# SPI_Board.net
KiCad netlist of a schematic drawn in Altium Designer
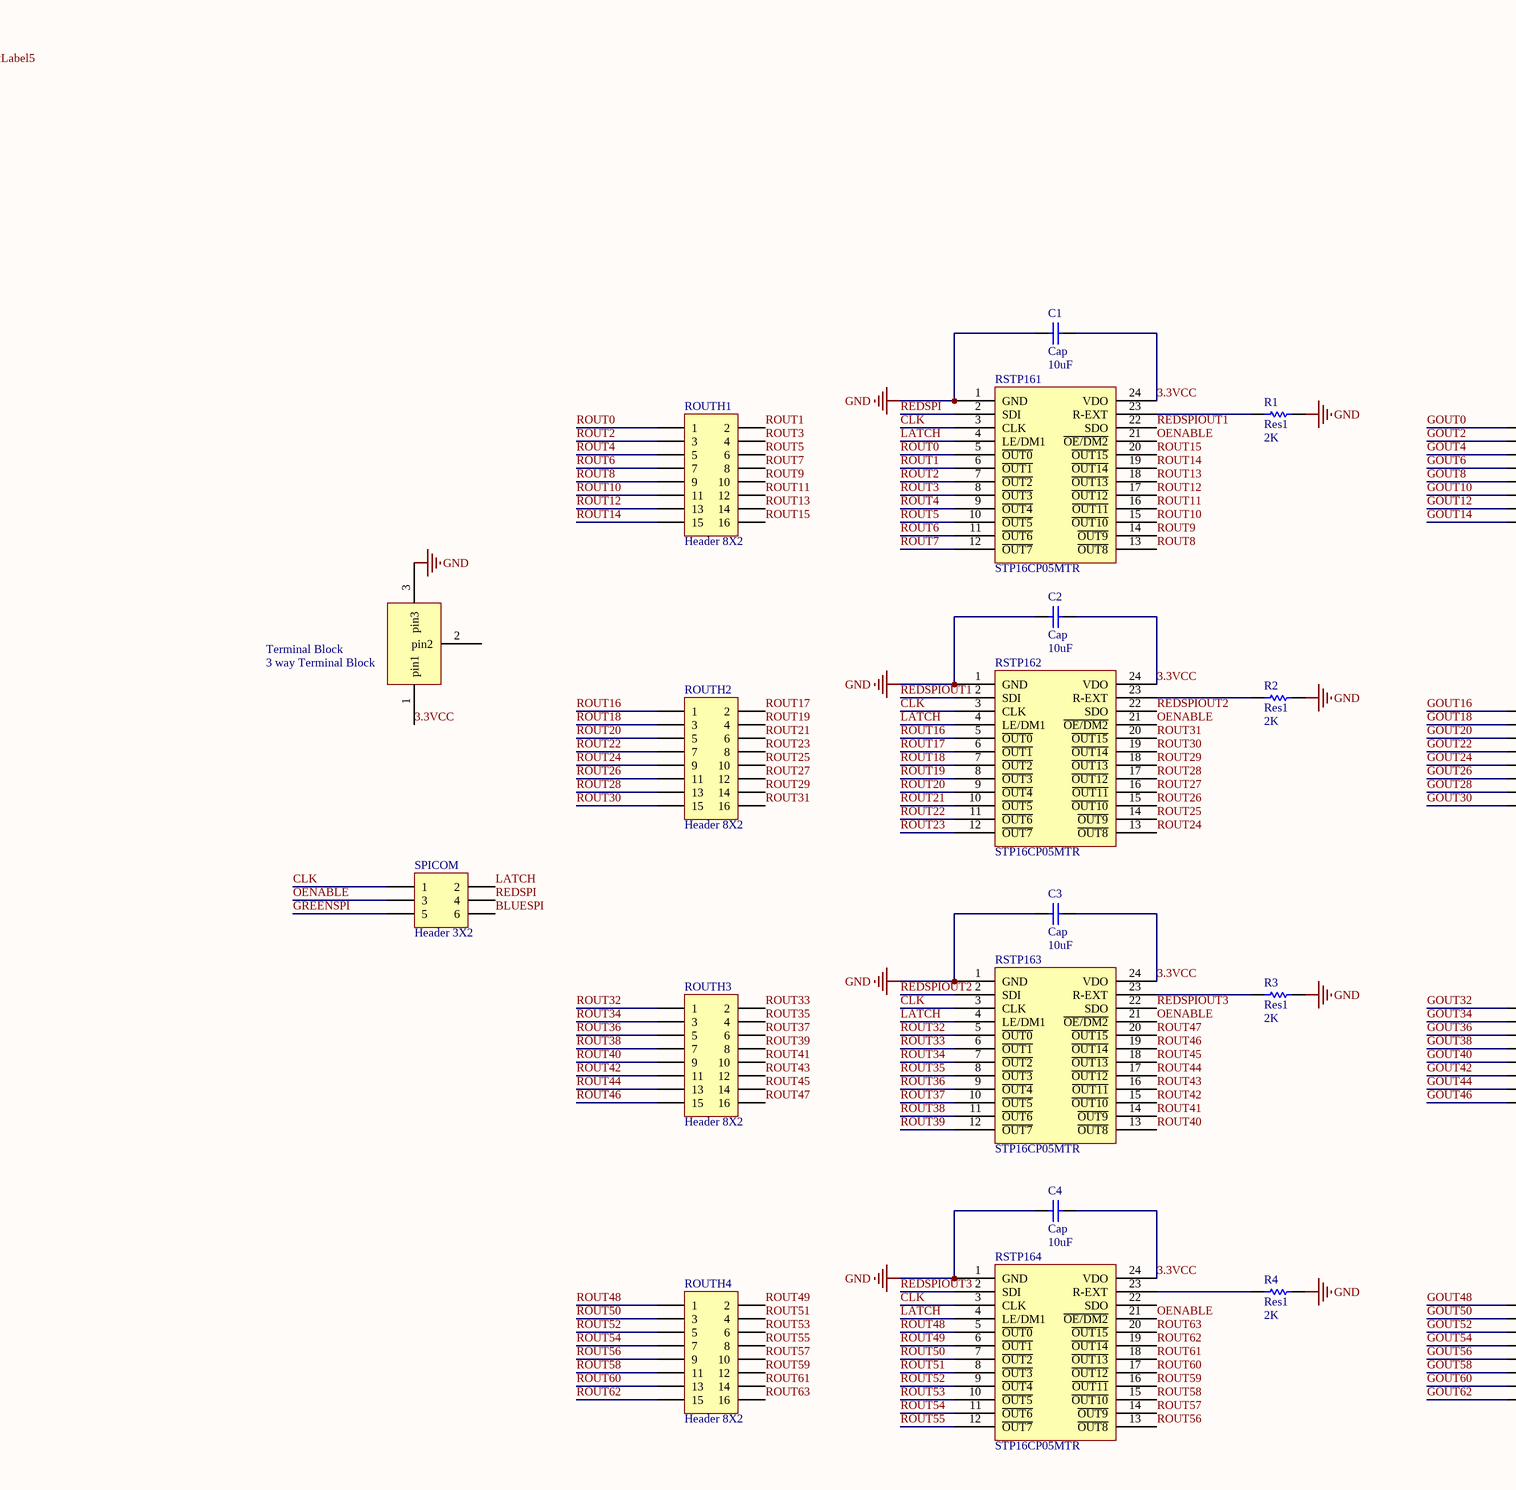
[diagram p0: SPI_Board.SchDoc, left]
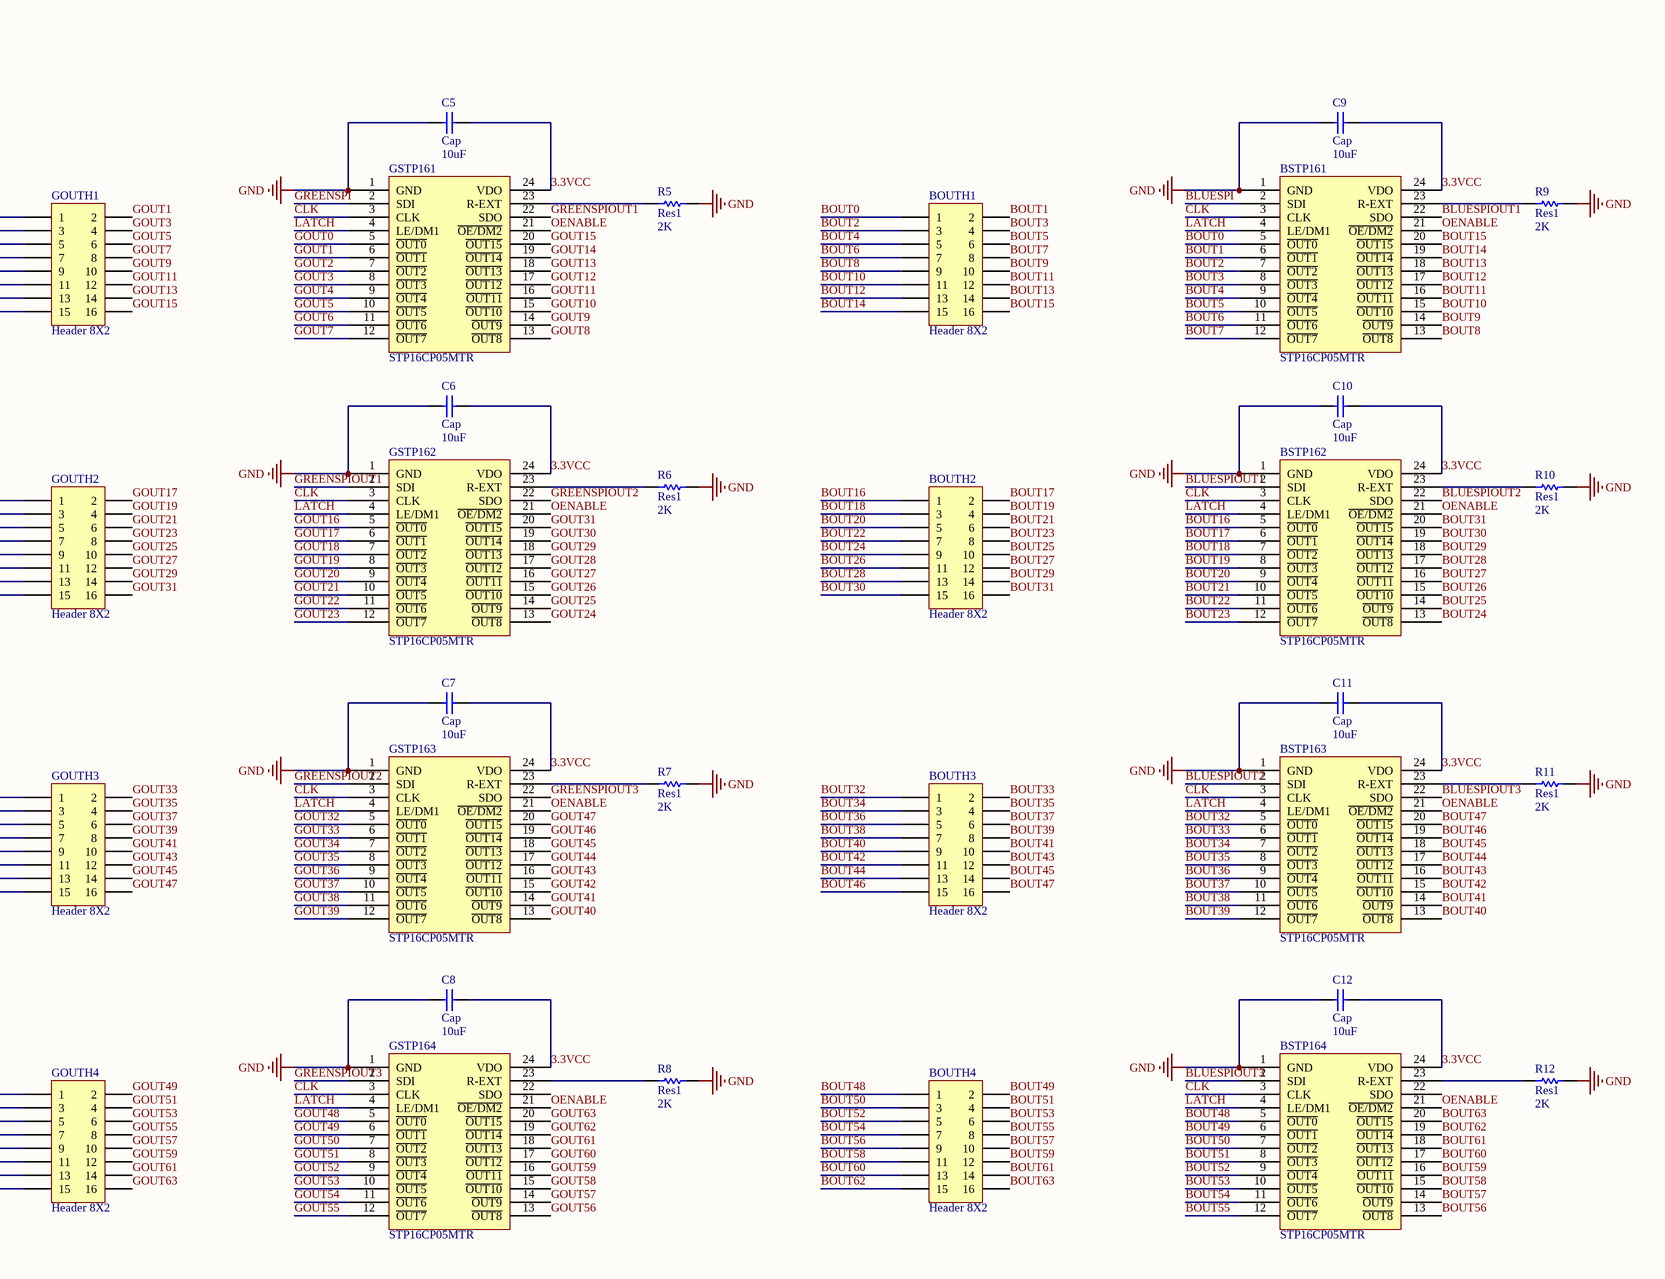
[diagram p1: SPI_Board.SchDoc, right]

(export (version "E")
  (design (tool "Eeschema 10.0.6"))
  (components
    (comp (ref "BOUTH1")
      (value "Header 8X2")
      (footprint "HDR2X8")
      (description "Header, 8-Pin, Dual row")
      (fields (field (name "PUBLISHER") "Altium Limited"))
      (libsource (lib "Miscellaneous Connectors") (part "Header 8X2"))
    )
    (comp (ref "BOUTH2")
      (value "Header 8X2")
      (footprint "HDR2X8")
      (description "Header, 8-Pin, Dual row")
      (fields (field (name "PUBLISHER") "Altium Limited"))
      (libsource (lib "Miscellaneous Connectors") (part "Header 8X2"))
    )
    (comp (ref "BOUTH3")
      (value "Header 8X2")
      (footprint "HDR2X8")
      (description "Header, 8-Pin, Dual row")
      (fields (field (name "PUBLISHER") "Altium Limited"))
      (libsource (lib "Miscellaneous Connectors") (part "Header 8X2"))
    )
    (comp (ref "BOUTH4")
      (value "Header 8X2")
      (footprint "HDR2X8")
      (description "Header, 8-Pin, Dual row")
      (fields (field (name "PUBLISHER") "Altium Limited"))
      (libsource (lib "Miscellaneous Connectors") (part "Header 8X2"))
    )
    (comp (ref "BSTP161")
      (value "STP16CP05MTR")
      (footprint "STP16CP05MTR-24N")
      (libsource (lib "STP16CP05MTR") (part "STP16CP05MTR"))
    )
    (comp (ref "BSTP162")
      (value "STP16CP05MTR")
      (footprint "STP16CP05MTR-24N")
      (libsource (lib "STP16CP05MTR") (part "STP16CP05MTR"))
    )
    (comp (ref "BSTP163")
      (value "STP16CP05MTR")
      (footprint "STP16CP05MTR-24N")
      (libsource (lib "STP16CP05MTR") (part "STP16CP05MTR"))
    )
    (comp (ref "BSTP164")
      (value "STP16CP05MTR")
      (footprint "STP16CP05MTR-24N")
      (libsource (lib "STP16CP05MTR") (part "STP16CP05MTR"))
    )
    (comp (ref "C1")
      (value "Cap")
      (footprint "RAD0.2A")
      (description "Capacitor")
      (fields (field (name "ALTIUM_VALUE") "10uF") (field (name "PUBLISHER") "Altium Limited"))
      (libsource (lib "Miscellaneous Devices") (part "Cap"))
    )
    (comp (ref "C2")
      (value "Cap")
      (footprint "RAD0.2A")
      (description "Capacitor")
      (fields (field (name "ALTIUM_VALUE") "10uF") (field (name "PUBLISHER") "Altium Limited"))
      (libsource (lib "Miscellaneous Devices") (part "Cap"))
    )
    (comp (ref "C3")
      (value "Cap")
      (footprint "RAD0.2A")
      (description "Capacitor")
      (fields (field (name "ALTIUM_VALUE") "10uF") (field (name "PUBLISHER") "Altium Limited"))
      (libsource (lib "Miscellaneous Devices") (part "Cap"))
    )
    (comp (ref "C4")
      (value "Cap")
      (footprint "RAD0.2A")
      (description "Capacitor")
      (fields (field (name "ALTIUM_VALUE") "10uF") (field (name "PUBLISHER") "Altium Limited"))
      (libsource (lib "Miscellaneous Devices") (part "Cap"))
    )
    (comp (ref "C5")
      (value "Cap")
      (footprint "RAD0.2A")
      (description "Capacitor")
      (fields (field (name "ALTIUM_VALUE") "10uF") (field (name "PUBLISHER") "Altium Limited"))
      (libsource (lib "Miscellaneous Devices") (part "Cap"))
    )
    (comp (ref "C6")
      (value "Cap")
      (footprint "RAD0.2A")
      (description "Capacitor")
      (fields (field (name "ALTIUM_VALUE") "10uF") (field (name "PUBLISHER") "Altium Limited"))
      (libsource (lib "Miscellaneous Devices") (part "Cap"))
    )
    (comp (ref "C7")
      (value "Cap")
      (footprint "RAD0.2A")
      (description "Capacitor")
      (fields (field (name "ALTIUM_VALUE") "10uF") (field (name "PUBLISHER") "Altium Limited"))
      (libsource (lib "Miscellaneous Devices") (part "Cap"))
    )
    (comp (ref "C8")
      (value "Cap")
      (footprint "RAD0.2A")
      (description "Capacitor")
      (fields (field (name "ALTIUM_VALUE") "10uF") (field (name "PUBLISHER") "Altium Limited"))
      (libsource (lib "Miscellaneous Devices") (part "Cap"))
    )
    (comp (ref "C9")
      (value "Cap")
      (footprint "RAD0.2A")
      (description "Capacitor")
      (fields (field (name "ALTIUM_VALUE") "10uF") (field (name "PUBLISHER") "Altium Limited"))
      (libsource (lib "Miscellaneous Devices") (part "Cap"))
    )
    (comp (ref "C10")
      (value "Cap")
      (footprint "RAD0.2A")
      (description "Capacitor")
      (fields (field (name "ALTIUM_VALUE") "10uF") (field (name "PUBLISHER") "Altium Limited"))
      (libsource (lib "Miscellaneous Devices") (part "Cap"))
    )
    (comp (ref "C11")
      (value "Cap")
      (footprint "RAD0.2A")
      (description "Capacitor")
      (fields (field (name "ALTIUM_VALUE") "10uF") (field (name "PUBLISHER") "Altium Limited"))
      (libsource (lib "Miscellaneous Devices") (part "Cap"))
    )
    (comp (ref "C12")
      (value "Cap")
      (footprint "RAD0.2A")
      (description "Capacitor")
      (fields (field (name "ALTIUM_VALUE") "10uF") (field (name "PUBLISHER") "Altium Limited"))
      (libsource (lib "Miscellaneous Devices") (part "Cap"))
    )
    (comp (ref "GOUTH1")
      (value "Header 8X2")
      (footprint "HDR2X8")
      (description "Header, 8-Pin, Dual row")
      (fields (field (name "PUBLISHER") "Altium Limited"))
      (libsource (lib "Miscellaneous Connectors") (part "Header 8X2"))
    )
    (comp (ref "GOUTH2")
      (value "Header 8X2")
      (footprint "HDR2X8")
      (description "Header, 8-Pin, Dual row")
      (fields (field (name "PUBLISHER") "Altium Limited"))
      (libsource (lib "Miscellaneous Connectors") (part "Header 8X2"))
    )
    (comp (ref "GOUTH3")
      (value "Header 8X2")
      (footprint "HDR2X8")
      (description "Header, 8-Pin, Dual row")
      (fields (field (name "PUBLISHER") "Altium Limited"))
      (libsource (lib "Miscellaneous Connectors") (part "Header 8X2"))
    )
    (comp (ref "GOUTH4")
      (value "Header 8X2")
      (footprint "HDR2X8")
      (description "Header, 8-Pin, Dual row")
      (fields (field (name "PUBLISHER") "Altium Limited"))
      (libsource (lib "Miscellaneous Connectors") (part "Header 8X2"))
    )
    (comp (ref "GSTP161")
      (value "STP16CP05MTR")
      (footprint "STP16CP05MTR-24N")
      (libsource (lib "STP16CP05MTR") (part "STP16CP05MTR"))
    )
    (comp (ref "GSTP162")
      (value "STP16CP05MTR")
      (footprint "STP16CP05MTR-24N")
      (libsource (lib "STP16CP05MTR") (part "STP16CP05MTR"))
    )
    (comp (ref "GSTP163")
      (value "STP16CP05MTR")
      (footprint "STP16CP05MTR-24N")
      (libsource (lib "STP16CP05MTR") (part "STP16CP05MTR"))
    )
    (comp (ref "GSTP164")
      (value "STP16CP05MTR")
      (footprint "STP16CP05MTR-24N")
      (libsource (lib "STP16CP05MTR") (part "STP16CP05MTR"))
    )
    (comp (ref "R1")
      (value "Res1")
      (footprint "AXIAL0.4")
      (description "Resistor")
      (fields (field (name "ALTIUM_VALUE") "2K") (field (name "PUBLISHER") "Altium Limited"))
      (libsource (lib "Miscellaneous Devices") (part "Res1"))
    )
    (comp (ref "R2")
      (value "Res1")
      (footprint "AXIAL0.4")
      (description "Resistor")
      (fields (field (name "ALTIUM_VALUE") "2K") (field (name "PUBLISHER") "Altium Limited"))
      (libsource (lib "Miscellaneous Devices") (part "Res1"))
    )
    (comp (ref "R3")
      (value "Res1")
      (footprint "AXIAL0.4")
      (description "Resistor")
      (fields (field (name "ALTIUM_VALUE") "2K") (field (name "PUBLISHER") "Altium Limited"))
      (libsource (lib "Miscellaneous Devices") (part "Res1"))
    )
    (comp (ref "R4")
      (value "Res1")
      (footprint "AXIAL0.4")
      (description "Resistor")
      (fields (field (name "ALTIUM_VALUE") "2K") (field (name "PUBLISHER") "Altium Limited"))
      (libsource (lib "Miscellaneous Devices") (part "Res1"))
    )
    (comp (ref "R5")
      (value "Res1")
      (footprint "AXIAL0.4")
      (description "Resistor")
      (fields (field (name "ALTIUM_VALUE") "2K") (field (name "PUBLISHER") "Altium Limited"))
      (libsource (lib "Miscellaneous Devices") (part "Res1"))
    )
    (comp (ref "R6")
      (value "Res1")
      (footprint "AXIAL0.4")
      (description "Resistor")
      (fields (field (name "ALTIUM_VALUE") "2K") (field (name "PUBLISHER") "Altium Limited"))
      (libsource (lib "Miscellaneous Devices") (part "Res1"))
    )
    (comp (ref "R7")
      (value "Res1")
      (footprint "AXIAL0.4")
      (description "Resistor")
      (fields (field (name "ALTIUM_VALUE") "2K") (field (name "PUBLISHER") "Altium Limited"))
      (libsource (lib "Miscellaneous Devices") (part "Res1"))
    )
    (comp (ref "R8")
      (value "Res1")
      (footprint "AXIAL0.4")
      (description "Resistor")
      (fields (field (name "ALTIUM_VALUE") "2K") (field (name "PUBLISHER") "Altium Limited"))
      (libsource (lib "Miscellaneous Devices") (part "Res1"))
    )
    (comp (ref "R9")
      (value "Res1")
      (footprint "AXIAL0.4")
      (description "Resistor")
      (fields (field (name "ALTIUM_VALUE") "2K") (field (name "PUBLISHER") "Altium Limited"))
      (libsource (lib "Miscellaneous Devices") (part "Res1"))
    )
    (comp (ref "R10")
      (value "Res1")
      (footprint "AXIAL0.4")
      (description "Resistor")
      (fields (field (name "ALTIUM_VALUE") "2K") (field (name "PUBLISHER") "Altium Limited"))
      (libsource (lib "Miscellaneous Devices") (part "Res1"))
    )
    (comp (ref "R11")
      (value "Res1")
      (footprint "AXIAL0.4")
      (description "Resistor")
      (fields (field (name "ALTIUM_VALUE") "2K") (field (name "PUBLISHER") "Altium Limited"))
      (libsource (lib "Miscellaneous Devices") (part "Res1"))
    )
    (comp (ref "R12")
      (value "Res1")
      (footprint "AXIAL0.4")
      (description "Resistor")
      (fields (field (name "ALTIUM_VALUE") "2K") (field (name "PUBLISHER") "Altium Limited"))
      (libsource (lib "Miscellaneous Devices") (part "Res1"))
    )
    (comp (ref "ROUTH1")
      (value "Header 8X2")
      (footprint "HDR2X8")
      (description "Header, 8-Pin, Dual row")
      (fields (field (name "PUBLISHER") "Altium Limited"))
      (libsource (lib "Miscellaneous Connectors") (part "Header 8X2"))
    )
    (comp (ref "ROUTH2")
      (value "Header 8X2")
      (footprint "HDR2X8")
      (description "Header, 8-Pin, Dual row")
      (fields (field (name "PUBLISHER") "Altium Limited"))
      (libsource (lib "Miscellaneous Connectors") (part "Header 8X2"))
    )
    (comp (ref "ROUTH3")
      (value "Header 8X2")
      (footprint "HDR2X8")
      (description "Header, 8-Pin, Dual row")
      (fields (field (name "PUBLISHER") "Altium Limited"))
      (libsource (lib "Miscellaneous Connectors") (part "Header 8X2"))
    )
    (comp (ref "ROUTH4")
      (value "Header 8X2")
      (footprint "HDR2X8")
      (description "Header, 8-Pin, Dual row")
      (fields (field (name "PUBLISHER") "Altium Limited"))
      (libsource (lib "Miscellaneous Connectors") (part "Header 8X2"))
    )
    (comp (ref "RSTP161")
      (value "STP16CP05MTR")
      (footprint "STP16CP05MTR-24N")
      (libsource (lib "STP16CP05MTR") (part "STP16CP05MTR"))
    )
    (comp (ref "RSTP162")
      (value "STP16CP05MTR")
      (footprint "STP16CP05MTR-24N")
      (libsource (lib "STP16CP05MTR") (part "STP16CP05MTR"))
    )
    (comp (ref "RSTP163")
      (value "STP16CP05MTR")
      (footprint "STP16CP05MTR-24N")
      (libsource (lib "STP16CP05MTR") (part "STP16CP05MTR"))
    )
    (comp (ref "RSTP164")
      (value "STP16CP05MTR")
      (footprint "STP16CP05MTR-24N")
      (libsource (lib "STP16CP05MTR") (part "STP16CP05MTR"))
    )
    (comp (ref "SPICOM")
      (value "Header 3X2")
      (footprint "HDR2X3")
      (description "Header, 3-Pin, Dual row")
      (fields (field (name "PUBLISHER") "Altium Limited"))
      (libsource (lib "Miscellaneous Connectors") (part "Header 3X2"))
    )
    (comp (ref "Terminal Block")
      (value "3 way Terminal Block")
      (footprint "PCTB3N")
      (libsource (lib "Terminal Block") (part "Component_1"))
    )
  )
  (nets
    (net (code "1") (name "/3.3VCC") (class "Default")
      (node (ref "BSTP161") (pin "24") (pinfunction "VDO_24") (pintype "passive"))
      (node (ref "BSTP162") (pin "24") (pinfunction "VDO_24") (pintype "passive"))
      (node (ref "BSTP163") (pin "24") (pinfunction "VDO_24") (pintype "passive"))
      (node (ref "BSTP164") (pin "24") (pinfunction "VDO_24") (pintype "passive"))
      (node (ref "C1") (pin "2") (pinfunction "2_2") (pintype "passive"))
      (node (ref "C10") (pin "2") (pinfunction "2_2") (pintype "passive"))
      (node (ref "C11") (pin "2") (pinfunction "2_2") (pintype "passive"))
      (node (ref "C12") (pin "2") (pinfunction "2_2") (pintype "passive"))
      (node (ref "C2") (pin "2") (pinfunction "2_2") (pintype "passive"))
      (node (ref "C3") (pin "2") (pinfunction "2_2") (pintype "passive"))
      (node (ref "C4") (pin "2") (pinfunction "2_2") (pintype "passive"))
      (node (ref "C5") (pin "2") (pinfunction "2_2") (pintype "passive"))
      (node (ref "C6") (pin "2") (pinfunction "2_2") (pintype "passive"))
      (node (ref "C7") (pin "2") (pinfunction "2_2") (pintype "passive"))
      (node (ref "C8") (pin "2") (pinfunction "2_2") (pintype "passive"))
      (node (ref "C9") (pin "2") (pinfunction "2_2") (pintype "passive"))
      (node (ref "GSTP161") (pin "24") (pinfunction "VDO_24") (pintype "passive"))
      (node (ref "GSTP162") (pin "24") (pinfunction "VDO_24") (pintype "passive"))
      (node (ref "GSTP163") (pin "24") (pinfunction "VDO_24") (pintype "passive"))
      (node (ref "GSTP164") (pin "24") (pinfunction "VDO_24") (pintype "passive"))
      (node (ref "RSTP161") (pin "24") (pinfunction "VDO_24") (pintype "passive"))
      (node (ref "RSTP162") (pin "24") (pinfunction "VDO_24") (pintype "passive"))
      (node (ref "RSTP163") (pin "24") (pinfunction "VDO_24") (pintype "passive"))
      (node (ref "RSTP164") (pin "24") (pinfunction "VDO_24") (pintype "passive"))
      (node (ref "Terminal Block") (pin "1") (pinfunction "pin1_1") (pintype "passive"))
    )
    (net (code "2") (name "/BLUESPI") (class "Default")
      (node (ref "BSTP161") (pin "2") (pinfunction "SDI_2") (pintype "passive"))
      (node (ref "SPICOM") (pin "6") (pinfunction "6_6") (pintype "passive"))
    )
    (net (code "3") (name "/BLUESPIOUT1") (class "Default")
      (node (ref "BSTP161") (pin "22") (pinfunction "SDO_22") (pintype "passive"))
      (node (ref "BSTP162") (pin "2") (pinfunction "SDI_2") (pintype "passive"))
    )
    (net (code "4") (name "/BLUESPIOUT2") (class "Default")
      (node (ref "BSTP162") (pin "22") (pinfunction "SDO_22") (pintype "passive"))
      (node (ref "BSTP163") (pin "2") (pinfunction "SDI_2") (pintype "passive"))
    )
    (net (code "5") (name "/BLUESPIOUT3") (class "Default")
      (node (ref "BSTP163") (pin "22") (pinfunction "SDO_22") (pintype "passive"))
      (node (ref "BSTP164") (pin "2") (pinfunction "SDI_2") (pintype "passive"))
    )
    (net (code "6") (name "/BOUT0") (class "Default")
      (node (ref "BOUTH1") (pin "1") (pinfunction "1_1") (pintype "passive"))
      (node (ref "BSTP161") (pin "5") (pinfunction "~{OUT0}_5") (pintype "passive"))
    )
    (net (code "7") (name "/BOUT1") (class "Default")
      (node (ref "BOUTH1") (pin "2") (pinfunction "2_2") (pintype "passive"))
      (node (ref "BSTP161") (pin "6") (pinfunction "~{OUT1}_6") (pintype "passive"))
    )
    (net (code "8") (name "/BOUT2") (class "Default")
      (node (ref "BOUTH1") (pin "3") (pinfunction "3_3") (pintype "passive"))
      (node (ref "BSTP161") (pin "7") (pinfunction "~{OUT2}_7") (pintype "passive"))
    )
    (net (code "9") (name "/BOUT3") (class "Default")
      (node (ref "BOUTH1") (pin "4") (pinfunction "4_4") (pintype "passive"))
      (node (ref "BSTP161") (pin "8") (pinfunction "~{OUT3}_8") (pintype "passive"))
    )
    (net (code "10") (name "/BOUT4") (class "Default")
      (node (ref "BOUTH1") (pin "5") (pinfunction "5_5") (pintype "passive"))
      (node (ref "BSTP161") (pin "9") (pinfunction "~{OUT4}_9") (pintype "passive"))
    )
    (net (code "11") (name "/BOUT5") (class "Default")
      (node (ref "BOUTH1") (pin "6") (pinfunction "6_6") (pintype "passive"))
      (node (ref "BSTP161") (pin "10") (pinfunction "~{OUT5}_10") (pintype "passive"))
    )
    (net (code "12") (name "/BOUT6") (class "Default")
      (node (ref "BOUTH1") (pin "7") (pinfunction "7_7") (pintype "passive"))
      (node (ref "BSTP161") (pin "11") (pinfunction "~{OUT6}_11") (pintype "passive"))
    )
    (net (code "13") (name "/BOUT7") (class "Default")
      (node (ref "BOUTH1") (pin "8") (pinfunction "8_8") (pintype "passive"))
      (node (ref "BSTP161") (pin "12") (pinfunction "~{OUT7}_12") (pintype "passive"))
    )
    (net (code "14") (name "/BOUT8") (class "Default")
      (node (ref "BOUTH1") (pin "9") (pinfunction "9_9") (pintype "passive"))
      (node (ref "BSTP161") (pin "13") (pinfunction "~{OUT8}_13") (pintype "passive"))
    )
    (net (code "15") (name "/BOUT9") (class "Default")
      (node (ref "BOUTH1") (pin "10") (pinfunction "10_10") (pintype "passive"))
      (node (ref "BSTP161") (pin "14") (pinfunction "~{OUT9}_14") (pintype "passive"))
    )
    (net (code "16") (name "/BOUT10") (class "Default")
      (node (ref "BOUTH1") (pin "11") (pinfunction "11_11") (pintype "passive"))
      (node (ref "BSTP161") (pin "15") (pinfunction "~{OUT10}_15") (pintype "passive"))
    )
    (net (code "17") (name "/BOUT11") (class "Default")
      (node (ref "BOUTH1") (pin "12") (pinfunction "12_12") (pintype "passive"))
      (node (ref "BSTP161") (pin "16") (pinfunction "~{OUT11}_16") (pintype "passive"))
    )
    (net (code "18") (name "/BOUT12") (class "Default")
      (node (ref "BOUTH1") (pin "13") (pinfunction "13_13") (pintype "passive"))
      (node (ref "BSTP161") (pin "17") (pinfunction "~{OUT12}_17") (pintype "passive"))
    )
    (net (code "19") (name "/BOUT13") (class "Default")
      (node (ref "BOUTH1") (pin "14") (pinfunction "14_14") (pintype "passive"))
      (node (ref "BSTP161") (pin "18") (pinfunction "~{OUT13}_18") (pintype "passive"))
    )
    (net (code "20") (name "/BOUT14") (class "Default")
      (node (ref "BOUTH1") (pin "15") (pinfunction "15_15") (pintype "passive"))
      (node (ref "BSTP161") (pin "19") (pinfunction "~{OUT14}_19") (pintype "passive"))
    )
    (net (code "21") (name "/BOUT15") (class "Default")
      (node (ref "BOUTH1") (pin "16") (pinfunction "16_16") (pintype "passive"))
      (node (ref "BSTP161") (pin "20") (pinfunction "~{OUT15}_20") (pintype "passive"))
    )
    (net (code "22") (name "/BOUT16") (class "Default")
      (node (ref "BOUTH2") (pin "1") (pinfunction "1_1") (pintype "passive"))
      (node (ref "BSTP162") (pin "5") (pinfunction "~{OUT0}_5") (pintype "passive"))
    )
    (net (code "23") (name "/BOUT17") (class "Default")
      (node (ref "BOUTH2") (pin "2") (pinfunction "2_2") (pintype "passive"))
      (node (ref "BSTP162") (pin "6") (pinfunction "~{OUT1}_6") (pintype "passive"))
    )
    (net (code "24") (name "/BOUT18") (class "Default")
      (node (ref "BOUTH2") (pin "3") (pinfunction "3_3") (pintype "passive"))
      (node (ref "BSTP162") (pin "7") (pinfunction "~{OUT2}_7") (pintype "passive"))
    )
    (net (code "25") (name "/BOUT19") (class "Default")
      (node (ref "BOUTH2") (pin "4") (pinfunction "4_4") (pintype "passive"))
      (node (ref "BSTP162") (pin "8") (pinfunction "~{OUT3}_8") (pintype "passive"))
    )
    (net (code "26") (name "/BOUT20") (class "Default")
      (node (ref "BOUTH2") (pin "5") (pinfunction "5_5") (pintype "passive"))
      (node (ref "BSTP162") (pin "9") (pinfunction "~{OUT4}_9") (pintype "passive"))
    )
    (net (code "27") (name "/BOUT21") (class "Default")
      (node (ref "BOUTH2") (pin "6") (pinfunction "6_6") (pintype "passive"))
      (node (ref "BSTP162") (pin "10") (pinfunction "~{OUT5}_10") (pintype "passive"))
    )
    (net (code "28") (name "/BOUT22") (class "Default")
      (node (ref "BOUTH2") (pin "7") (pinfunction "7_7") (pintype "passive"))
      (node (ref "BSTP162") (pin "11") (pinfunction "~{OUT6}_11") (pintype "passive"))
    )
    (net (code "29") (name "/BOUT23") (class "Default")
      (node (ref "BOUTH2") (pin "8") (pinfunction "8_8") (pintype "passive"))
      (node (ref "BSTP162") (pin "12") (pinfunction "~{OUT7}_12") (pintype "passive"))
    )
    (net (code "30") (name "/BOUT24") (class "Default")
      (node (ref "BOUTH2") (pin "9") (pinfunction "9_9") (pintype "passive"))
      (node (ref "BSTP162") (pin "13") (pinfunction "~{OUT8}_13") (pintype "passive"))
    )
    (net (code "31") (name "/BOUT25") (class "Default")
      (node (ref "BOUTH2") (pin "10") (pinfunction "10_10") (pintype "passive"))
      (node (ref "BSTP162") (pin "14") (pinfunction "~{OUT9}_14") (pintype "passive"))
    )
    (net (code "32") (name "/BOUT26") (class "Default")
      (node (ref "BOUTH2") (pin "11") (pinfunction "11_11") (pintype "passive"))
      (node (ref "BSTP162") (pin "15") (pinfunction "~{OUT10}_15") (pintype "passive"))
    )
    (net (code "33") (name "/BOUT27") (class "Default")
      (node (ref "BOUTH2") (pin "12") (pinfunction "12_12") (pintype "passive"))
      (node (ref "BSTP162") (pin "16") (pinfunction "~{OUT11}_16") (pintype "passive"))
    )
    (net (code "34") (name "/BOUT28") (class "Default")
      (node (ref "BOUTH2") (pin "13") (pinfunction "13_13") (pintype "passive"))
      (node (ref "BSTP162") (pin "17") (pinfunction "~{OUT12}_17") (pintype "passive"))
    )
    (net (code "35") (name "/BOUT29") (class "Default")
      (node (ref "BOUTH2") (pin "14") (pinfunction "14_14") (pintype "passive"))
      (node (ref "BSTP162") (pin "18") (pinfunction "~{OUT13}_18") (pintype "passive"))
    )
    (net (code "36") (name "/BOUT30") (class "Default")
      (node (ref "BOUTH2") (pin "15") (pinfunction "15_15") (pintype "passive"))
      (node (ref "BSTP162") (pin "19") (pinfunction "~{OUT14}_19") (pintype "passive"))
    )
    (net (code "37") (name "/BOUT31") (class "Default")
      (node (ref "BOUTH2") (pin "16") (pinfunction "16_16") (pintype "passive"))
      (node (ref "BSTP162") (pin "20") (pinfunction "~{OUT15}_20") (pintype "passive"))
    )
    (net (code "38") (name "/BOUT32") (class "Default")
      (node (ref "BOUTH3") (pin "1") (pinfunction "1_1") (pintype "passive"))
      (node (ref "BSTP163") (pin "5") (pinfunction "~{OUT0}_5") (pintype "passive"))
    )
    (net (code "39") (name "/BOUT33") (class "Default")
      (node (ref "BOUTH3") (pin "2") (pinfunction "2_2") (pintype "passive"))
      (node (ref "BSTP163") (pin "6") (pinfunction "~{OUT1}_6") (pintype "passive"))
    )
    (net (code "40") (name "/BOUT34") (class "Default")
      (node (ref "BOUTH3") (pin "3") (pinfunction "3_3") (pintype "passive"))
      (node (ref "BSTP163") (pin "7") (pinfunction "~{OUT2}_7") (pintype "passive"))
    )
    (net (code "41") (name "/BOUT35") (class "Default")
      (node (ref "BOUTH3") (pin "4") (pinfunction "4_4") (pintype "passive"))
      (node (ref "BSTP163") (pin "8") (pinfunction "~{OUT3}_8") (pintype "passive"))
    )
    (net (code "42") (name "/BOUT36") (class "Default")
      (node (ref "BOUTH3") (pin "5") (pinfunction "5_5") (pintype "passive"))
      (node (ref "BSTP163") (pin "9") (pinfunction "~{OUT4}_9") (pintype "passive"))
    )
    (net (code "43") (name "/BOUT37") (class "Default")
      (node (ref "BOUTH3") (pin "6") (pinfunction "6_6") (pintype "passive"))
      (node (ref "BSTP163") (pin "10") (pinfunction "~{OUT5}_10") (pintype "passive"))
    )
    (net (code "44") (name "/BOUT38") (class "Default")
      (node (ref "BOUTH3") (pin "7") (pinfunction "7_7") (pintype "passive"))
      (node (ref "BSTP163") (pin "11") (pinfunction "~{OUT6}_11") (pintype "passive"))
    )
    (net (code "45") (name "/BOUT39") (class "Default")
      (node (ref "BOUTH3") (pin "8") (pinfunction "8_8") (pintype "passive"))
      (node (ref "BSTP163") (pin "12") (pinfunction "~{OUT7}_12") (pintype "passive"))
    )
    (net (code "46") (name "/BOUT40") (class "Default")
      (node (ref "BOUTH3") (pin "9") (pinfunction "9_9") (pintype "passive"))
      (node (ref "BSTP163") (pin "13") (pinfunction "~{OUT8}_13") (pintype "passive"))
    )
    (net (code "47") (name "/BOUT41") (class "Default")
      (node (ref "BOUTH3") (pin "10") (pinfunction "10_10") (pintype "passive"))
      (node (ref "BSTP163") (pin "14") (pinfunction "~{OUT9}_14") (pintype "passive"))
    )
    (net (code "48") (name "/BOUT42") (class "Default")
      (node (ref "BOUTH3") (pin "11") (pinfunction "11_11") (pintype "passive"))
      (node (ref "BSTP163") (pin "15") (pinfunction "~{OUT10}_15") (pintype "passive"))
    )
    (net (code "49") (name "/BOUT43") (class "Default")
      (node (ref "BOUTH3") (pin "12") (pinfunction "12_12") (pintype "passive"))
      (node (ref "BSTP163") (pin "16") (pinfunction "~{OUT11}_16") (pintype "passive"))
    )
    (net (code "50") (name "/BOUT44") (class "Default")
      (node (ref "BOUTH3") (pin "13") (pinfunction "13_13") (pintype "passive"))
      (node (ref "BSTP163") (pin "17") (pinfunction "~{OUT12}_17") (pintype "passive"))
    )
    (net (code "51") (name "/BOUT45") (class "Default")
      (node (ref "BOUTH3") (pin "14") (pinfunction "14_14") (pintype "passive"))
      (node (ref "BSTP163") (pin "18") (pinfunction "~{OUT13}_18") (pintype "passive"))
    )
    (net (code "52") (name "/BOUT46") (class "Default")
      (node (ref "BOUTH3") (pin "15") (pinfunction "15_15") (pintype "passive"))
      (node (ref "BSTP163") (pin "19") (pinfunction "~{OUT14}_19") (pintype "passive"))
    )
    (net (code "53") (name "/BOUT47") (class "Default")
      (node (ref "BOUTH3") (pin "16") (pinfunction "16_16") (pintype "passive"))
      (node (ref "BSTP163") (pin "20") (pinfunction "~{OUT15}_20") (pintype "passive"))
    )
    (net (code "54") (name "/BOUT48") (class "Default")
      (node (ref "BOUTH4") (pin "1") (pinfunction "1_1") (pintype "passive"))
      (node (ref "BSTP164") (pin "5") (pinfunction "~{OUT0}_5") (pintype "passive"))
    )
    (net (code "55") (name "/BOUT49") (class "Default")
      (node (ref "BOUTH4") (pin "2") (pinfunction "2_2") (pintype "passive"))
      (node (ref "BSTP164") (pin "6") (pinfunction "~{OUT1}_6") (pintype "passive"))
    )
    (net (code "56") (name "/BOUT50") (class "Default")
      (node (ref "BOUTH4") (pin "3") (pinfunction "3_3") (pintype "passive"))
      (node (ref "BSTP164") (pin "7") (pinfunction "~{OUT2}_7") (pintype "passive"))
    )
    (net (code "57") (name "/BOUT51") (class "Default")
      (node (ref "BOUTH4") (pin "4") (pinfunction "4_4") (pintype "passive"))
      (node (ref "BSTP164") (pin "8") (pinfunction "~{OUT3}_8") (pintype "passive"))
    )
    (net (code "58") (name "/BOUT52") (class "Default")
      (node (ref "BOUTH4") (pin "5") (pinfunction "5_5") (pintype "passive"))
      (node (ref "BSTP164") (pin "9") (pinfunction "~{OUT4}_9") (pintype "passive"))
    )
    (net (code "59") (name "/BOUT53") (class "Default")
      (node (ref "BOUTH4") (pin "6") (pinfunction "6_6") (pintype "passive"))
      (node (ref "BSTP164") (pin "10") (pinfunction "~{OUT5}_10") (pintype "passive"))
    )
    (net (code "60") (name "/BOUT54") (class "Default")
      (node (ref "BOUTH4") (pin "7") (pinfunction "7_7") (pintype "passive"))
      (node (ref "BSTP164") (pin "11") (pinfunction "~{OUT6}_11") (pintype "passive"))
    )
    (net (code "61") (name "/BOUT55") (class "Default")
      (node (ref "BOUTH4") (pin "8") (pinfunction "8_8") (pintype "passive"))
      (node (ref "BSTP164") (pin "12") (pinfunction "~{OUT7}_12") (pintype "passive"))
    )
    (net (code "62") (name "/BOUT56") (class "Default")
      (node (ref "BOUTH4") (pin "9") (pinfunction "9_9") (pintype "passive"))
      (node (ref "BSTP164") (pin "13") (pinfunction "~{OUT8}_13") (pintype "passive"))
    )
    (net (code "63") (name "/BOUT57") (class "Default")
      (node (ref "BOUTH4") (pin "10") (pinfunction "10_10") (pintype "passive"))
      (node (ref "BSTP164") (pin "14") (pinfunction "~{OUT9}_14") (pintype "passive"))
    )
    (net (code "64") (name "/BOUT58") (class "Default")
      (node (ref "BOUTH4") (pin "11") (pinfunction "11_11") (pintype "passive"))
      (node (ref "BSTP164") (pin "15") (pinfunction "~{OUT10}_15") (pintype "passive"))
    )
    (net (code "65") (name "/BOUT59") (class "Default")
      (node (ref "BOUTH4") (pin "12") (pinfunction "12_12") (pintype "passive"))
      (node (ref "BSTP164") (pin "16") (pinfunction "~{OUT11}_16") (pintype "passive"))
    )
    (net (code "66") (name "/BOUT60") (class "Default")
      (node (ref "BOUTH4") (pin "13") (pinfunction "13_13") (pintype "passive"))
      (node (ref "BSTP164") (pin "17") (pinfunction "~{OUT12}_17") (pintype "passive"))
    )
    (net (code "67") (name "/BOUT61") (class "Default")
      (node (ref "BOUTH4") (pin "14") (pinfunction "14_14") (pintype "passive"))
      (node (ref "BSTP164") (pin "18") (pinfunction "~{OUT13}_18") (pintype "passive"))
    )
    (net (code "68") (name "/BOUT62") (class "Default")
      (node (ref "BOUTH4") (pin "15") (pinfunction "15_15") (pintype "passive"))
      (node (ref "BSTP164") (pin "19") (pinfunction "~{OUT14}_19") (pintype "passive"))
    )
    (net (code "69") (name "/BOUT63") (class "Default")
      (node (ref "BOUTH4") (pin "16") (pinfunction "16_16") (pintype "passive"))
      (node (ref "BSTP164") (pin "20") (pinfunction "~{OUT15}_20") (pintype "passive"))
    )
    (net (code "70") (name "/CLK") (class "Default")
      (node (ref "BSTP161") (pin "3") (pinfunction "CLK_3") (pintype "passive"))
      (node (ref "BSTP162") (pin "3") (pinfunction "CLK_3") (pintype "passive"))
      (node (ref "BSTP163") (pin "3") (pinfunction "CLK_3") (pintype "passive"))
      (node (ref "BSTP164") (pin "3") (pinfunction "CLK_3") (pintype "passive"))
      (node (ref "GSTP161") (pin "3") (pinfunction "CLK_3") (pintype "passive"))
      (node (ref "GSTP162") (pin "3") (pinfunction "CLK_3") (pintype "passive"))
      (node (ref "GSTP163") (pin "3") (pinfunction "CLK_3") (pintype "passive"))
      (node (ref "GSTP164") (pin "3") (pinfunction "CLK_3") (pintype "passive"))
      (node (ref "RSTP161") (pin "3") (pinfunction "CLK_3") (pintype "passive"))
      (node (ref "RSTP162") (pin "3") (pinfunction "CLK_3") (pintype "passive"))
      (node (ref "RSTP163") (pin "3") (pinfunction "CLK_3") (pintype "passive"))
      (node (ref "RSTP164") (pin "3") (pinfunction "CLK_3") (pintype "passive"))
      (node (ref "SPICOM") (pin "1") (pinfunction "1_1") (pintype "passive"))
    )
    (net (code "71") (name "/GOUT0") (class "Default")
      (node (ref "GOUTH1") (pin "1") (pinfunction "1_1") (pintype "passive"))
      (node (ref "GSTP161") (pin "5") (pinfunction "~{OUT0}_5") (pintype "passive"))
    )
    (net (code "72") (name "/GOUT1") (class "Default")
      (node (ref "GOUTH1") (pin "2") (pinfunction "2_2") (pintype "passive"))
      (node (ref "GSTP161") (pin "6") (pinfunction "~{OUT1}_6") (pintype "passive"))
    )
    (net (code "73") (name "/GOUT2") (class "Default")
      (node (ref "GOUTH1") (pin "3") (pinfunction "3_3") (pintype "passive"))
      (node (ref "GSTP161") (pin "7") (pinfunction "~{OUT2}_7") (pintype "passive"))
    )
    (net (code "74") (name "/GOUT3") (class "Default")
      (node (ref "GOUTH1") (pin "4") (pinfunction "4_4") (pintype "passive"))
      (node (ref "GSTP161") (pin "8") (pinfunction "~{OUT3}_8") (pintype "passive"))
    )
    (net (code "75") (name "/GOUT4") (class "Default")
      (node (ref "GOUTH1") (pin "5") (pinfunction "5_5") (pintype "passive"))
      (node (ref "GSTP161") (pin "9") (pinfunction "~{OUT4}_9") (pintype "passive"))
    )
    (net (code "76") (name "/GOUT5") (class "Default")
      (node (ref "GOUTH1") (pin "6") (pinfunction "6_6") (pintype "passive"))
      (node (ref "GSTP161") (pin "10") (pinfunction "~{OUT5}_10") (pintype "passive"))
    )
    (net (code "77") (name "/GOUT6") (class "Default")
      (node (ref "GOUTH1") (pin "7") (pinfunction "7_7") (pintype "passive"))
      (node (ref "GSTP161") (pin "11") (pinfunction "~{OUT6}_11") (pintype "passive"))
    )
    (net (code "78") (name "/GOUT7") (class "Default")
      (node (ref "GOUTH1") (pin "8") (pinfunction "8_8") (pintype "passive"))
      (node (ref "GSTP161") (pin "12") (pinfunction "~{OUT7}_12") (pintype "passive"))
    )
    (net (code "79") (name "/GOUT8") (class "Default")
      (node (ref "GOUTH1") (pin "9") (pinfunction "9_9") (pintype "passive"))
      (node (ref "GSTP161") (pin "13") (pinfunction "~{OUT8}_13") (pintype "passive"))
    )
    (net (code "80") (name "/GOUT9") (class "Default")
      (node (ref "GOUTH1") (pin "10") (pinfunction "10_10") (pintype "passive"))
      (node (ref "GSTP161") (pin "14") (pinfunction "~{OUT9}_14") (pintype "passive"))
    )
    (net (code "81") (name "/GOUT10") (class "Default")
      (node (ref "GOUTH1") (pin "11") (pinfunction "11_11") (pintype "passive"))
      (node (ref "GSTP161") (pin "15") (pinfunction "~{OUT10}_15") (pintype "passive"))
    )
    (net (code "82") (name "/GOUT11") (class "Default")
      (node (ref "GOUTH1") (pin "12") (pinfunction "12_12") (pintype "passive"))
      (node (ref "GSTP161") (pin "16") (pinfunction "~{OUT11}_16") (pintype "passive"))
    )
    (net (code "83") (name "/GOUT12") (class "Default")
      (node (ref "GOUTH1") (pin "13") (pinfunction "13_13") (pintype "passive"))
      (node (ref "GSTP161") (pin "17") (pinfunction "~{OUT12}_17") (pintype "passive"))
    )
    (net (code "84") (name "/GOUT13") (class "Default")
      (node (ref "GOUTH1") (pin "14") (pinfunction "14_14") (pintype "passive"))
      (node (ref "GSTP161") (pin "18") (pinfunction "~{OUT13}_18") (pintype "passive"))
    )
    (net (code "85") (name "/GOUT14") (class "Default")
      (node (ref "GOUTH1") (pin "15") (pinfunction "15_15") (pintype "passive"))
      (node (ref "GSTP161") (pin "19") (pinfunction "~{OUT14}_19") (pintype "passive"))
    )
    (net (code "86") (name "/GOUT15") (class "Default")
      (node (ref "GOUTH1") (pin "16") (pinfunction "16_16") (pintype "passive"))
      (node (ref "GSTP161") (pin "20") (pinfunction "~{OUT15}_20") (pintype "passive"))
    )
    (net (code "87") (name "/GOUT16") (class "Default")
      (node (ref "GOUTH2") (pin "1") (pinfunction "1_1") (pintype "passive"))
      (node (ref "GSTP162") (pin "5") (pinfunction "~{OUT0}_5") (pintype "passive"))
    )
    (net (code "88") (name "/GOUT17") (class "Default")
      (node (ref "GOUTH2") (pin "2") (pinfunction "2_2") (pintype "passive"))
      (node (ref "GSTP162") (pin "6") (pinfunction "~{OUT1}_6") (pintype "passive"))
    )
    (net (code "89") (name "/GOUT18") (class "Default")
      (node (ref "GOUTH2") (pin "3") (pinfunction "3_3") (pintype "passive"))
      (node (ref "GSTP162") (pin "7") (pinfunction "~{OUT2}_7") (pintype "passive"))
    )
    (net (code "90") (name "/GOUT19") (class "Default")
      (node (ref "GOUTH2") (pin "4") (pinfunction "4_4") (pintype "passive"))
      (node (ref "GSTP162") (pin "8") (pinfunction "~{OUT3}_8") (pintype "passive"))
    )
    (net (code "91") (name "/GOUT20") (class "Default")
      (node (ref "GOUTH2") (pin "5") (pinfunction "5_5") (pintype "passive"))
      (node (ref "GSTP162") (pin "9") (pinfunction "~{OUT4}_9") (pintype "passive"))
    )
    (net (code "92") (name "/GOUT21") (class "Default")
      (node (ref "GOUTH2") (pin "6") (pinfunction "6_6") (pintype "passive"))
      (node (ref "GSTP162") (pin "10") (pinfunction "~{OUT5}_10") (pintype "passive"))
    )
    (net (code "93") (name "/GOUT22") (class "Default")
      (node (ref "GOUTH2") (pin "7") (pinfunction "7_7") (pintype "passive"))
      (node (ref "GSTP162") (pin "11") (pinfunction "~{OUT6}_11") (pintype "passive"))
    )
    (net (code "94") (name "/GOUT23") (class "Default")
      (node (ref "GOUTH2") (pin "8") (pinfunction "8_8") (pintype "passive"))
      (node (ref "GSTP162") (pin "12") (pinfunction "~{OUT7}_12") (pintype "passive"))
    )
    (net (code "95") (name "/GOUT24") (class "Default")
      (node (ref "GOUTH2") (pin "9") (pinfunction "9_9") (pintype "passive"))
      (node (ref "GSTP162") (pin "13") (pinfunction "~{OUT8}_13") (pintype "passive"))
    )
    (net (code "96") (name "/GOUT25") (class "Default")
      (node (ref "GOUTH2") (pin "10") (pinfunction "10_10") (pintype "passive"))
      (node (ref "GSTP162") (pin "14") (pinfunction "~{OUT9}_14") (pintype "passive"))
    )
    (net (code "97") (name "/GOUT26") (class "Default")
      (node (ref "GOUTH2") (pin "11") (pinfunction "11_11") (pintype "passive"))
      (node (ref "GSTP162") (pin "15") (pinfunction "~{OUT10}_15") (pintype "passive"))
    )
    (net (code "98") (name "/GOUT27") (class "Default")
      (node (ref "GOUTH2") (pin "12") (pinfunction "12_12") (pintype "passive"))
      (node (ref "GSTP162") (pin "16") (pinfunction "~{OUT11}_16") (pintype "passive"))
    )
    (net (code "99") (name "/GOUT28") (class "Default")
      (node (ref "GOUTH2") (pin "13") (pinfunction "13_13") (pintype "passive"))
      (node (ref "GSTP162") (pin "17") (pinfunction "~{OUT12}_17") (pintype "passive"))
    )
    (net (code "100") (name "/GOUT29") (class "Default")
      (node (ref "GOUTH2") (pin "14") (pinfunction "14_14") (pintype "passive"))
      (node (ref "GSTP162") (pin "18") (pinfunction "~{OUT13}_18") (pintype "passive"))
    )
    (net (code "101") (name "/GOUT30") (class "Default")
      (node (ref "GOUTH2") (pin "15") (pinfunction "15_15") (pintype "passive"))
      (node (ref "GSTP162") (pin "19") (pinfunction "~{OUT14}_19") (pintype "passive"))
    )
    (net (code "102") (name "/GOUT31") (class "Default")
      (node (ref "GOUTH2") (pin "16") (pinfunction "16_16") (pintype "passive"))
      (node (ref "GSTP162") (pin "20") (pinfunction "~{OUT15}_20") (pintype "passive"))
    )
    (net (code "103") (name "/GOUT32") (class "Default")
      (node (ref "GOUTH3") (pin "1") (pinfunction "1_1") (pintype "passive"))
      (node (ref "GSTP163") (pin "5") (pinfunction "~{OUT0}_5") (pintype "passive"))
    )
    (net (code "104") (name "/GOUT33") (class "Default")
      (node (ref "GOUTH3") (pin "2") (pinfunction "2_2") (pintype "passive"))
      (node (ref "GSTP163") (pin "6") (pinfunction "~{OUT1}_6") (pintype "passive"))
    )
    (net (code "105") (name "/GOUT34") (class "Default")
      (node (ref "GOUTH3") (pin "3") (pinfunction "3_3") (pintype "passive"))
      (node (ref "GSTP163") (pin "7") (pinfunction "~{OUT2}_7") (pintype "passive"))
    )
    (net (code "106") (name "/GOUT35") (class "Default")
      (node (ref "GOUTH3") (pin "4") (pinfunction "4_4") (pintype "passive"))
      (node (ref "GSTP163") (pin "8") (pinfunction "~{OUT3}_8") (pintype "passive"))
    )
    (net (code "107") (name "/GOUT36") (class "Default")
      (node (ref "GOUTH3") (pin "5") (pinfunction "5_5") (pintype "passive"))
      (node (ref "GSTP163") (pin "9") (pinfunction "~{OUT4}_9") (pintype "passive"))
    )
    (net (code "108") (name "/GOUT37") (class "Default")
      (node (ref "GOUTH3") (pin "6") (pinfunction "6_6") (pintype "passive"))
      (node (ref "GSTP163") (pin "10") (pinfunction "~{OUT5}_10") (pintype "passive"))
    )
    (net (code "109") (name "/GOUT38") (class "Default")
      (node (ref "GOUTH3") (pin "7") (pinfunction "7_7") (pintype "passive"))
      (node (ref "GSTP163") (pin "11") (pinfunction "~{OUT6}_11") (pintype "passive"))
    )
    (net (code "110") (name "/GOUT39") (class "Default")
      (node (ref "GOUTH3") (pin "8") (pinfunction "8_8") (pintype "passive"))
      (node (ref "GSTP163") (pin "12") (pinfunction "~{OUT7}_12") (pintype "passive"))
    )
    (net (code "111") (name "/GOUT40") (class "Default")
      (node (ref "GOUTH3") (pin "9") (pinfunction "9_9") (pintype "passive"))
      (node (ref "GSTP163") (pin "13") (pinfunction "~{OUT8}_13") (pintype "passive"))
    )
    (net (code "112") (name "/GOUT41") (class "Default")
      (node (ref "GOUTH3") (pin "10") (pinfunction "10_10") (pintype "passive"))
      (node (ref "GSTP163") (pin "14") (pinfunction "~{OUT9}_14") (pintype "passive"))
    )
    (net (code "113") (name "/GOUT42") (class "Default")
      (node (ref "GOUTH3") (pin "11") (pinfunction "11_11") (pintype "passive"))
      (node (ref "GSTP163") (pin "15") (pinfunction "~{OUT10}_15") (pintype "passive"))
    )
    (net (code "114") (name "/GOUT43") (class "Default")
      (node (ref "GOUTH3") (pin "12") (pinfunction "12_12") (pintype "passive"))
      (node (ref "GSTP163") (pin "16") (pinfunction "~{OUT11}_16") (pintype "passive"))
    )
    (net (code "115") (name "/GOUT44") (class "Default")
      (node (ref "GOUTH3") (pin "13") (pinfunction "13_13") (pintype "passive"))
      (node (ref "GSTP163") (pin "17") (pinfunction "~{OUT12}_17") (pintype "passive"))
    )
    (net (code "116") (name "/GOUT45") (class "Default")
      (node (ref "GOUTH3") (pin "14") (pinfunction "14_14") (pintype "passive"))
      (node (ref "GSTP163") (pin "18") (pinfunction "~{OUT13}_18") (pintype "passive"))
    )
    (net (code "117") (name "/GOUT46") (class "Default")
      (node (ref "GOUTH3") (pin "15") (pinfunction "15_15") (pintype "passive"))
      (node (ref "GSTP163") (pin "19") (pinfunction "~{OUT14}_19") (pintype "passive"))
    )
    (net (code "118") (name "/GOUT47") (class "Default")
      (node (ref "GOUTH3") (pin "16") (pinfunction "16_16") (pintype "passive"))
      (node (ref "GSTP163") (pin "20") (pinfunction "~{OUT15}_20") (pintype "passive"))
    )
    (net (code "119") (name "/GOUT48") (class "Default")
      (node (ref "GOUTH4") (pin "1") (pinfunction "1_1") (pintype "passive"))
      (node (ref "GSTP164") (pin "5") (pinfunction "~{OUT0}_5") (pintype "passive"))
    )
    (net (code "120") (name "/GOUT49") (class "Default")
      (node (ref "GOUTH4") (pin "2") (pinfunction "2_2") (pintype "passive"))
      (node (ref "GSTP164") (pin "6") (pinfunction "~{OUT1}_6") (pintype "passive"))
    )
    (net (code "121") (name "/GOUT50") (class "Default")
      (node (ref "GOUTH4") (pin "3") (pinfunction "3_3") (pintype "passive"))
      (node (ref "GSTP164") (pin "7") (pinfunction "~{OUT2}_7") (pintype "passive"))
    )
    (net (code "122") (name "/GOUT51") (class "Default")
      (node (ref "GOUTH4") (pin "4") (pinfunction "4_4") (pintype "passive"))
      (node (ref "GSTP164") (pin "8") (pinfunction "~{OUT3}_8") (pintype "passive"))
    )
    (net (code "123") (name "/GOUT52") (class "Default")
      (node (ref "GOUTH4") (pin "5") (pinfunction "5_5") (pintype "passive"))
      (node (ref "GSTP164") (pin "9") (pinfunction "~{OUT4}_9") (pintype "passive"))
    )
    (net (code "124") (name "/GOUT53") (class "Default")
      (node (ref "GOUTH4") (pin "6") (pinfunction "6_6") (pintype "passive"))
      (node (ref "GSTP164") (pin "10") (pinfunction "~{OUT5}_10") (pintype "passive"))
    )
    (net (code "125") (name "/GOUT54") (class "Default")
      (node (ref "GOUTH4") (pin "7") (pinfunction "7_7") (pintype "passive"))
      (node (ref "GSTP164") (pin "11") (pinfunction "~{OUT6}_11") (pintype "passive"))
    )
    (net (code "126") (name "/GOUT55") (class "Default")
      (node (ref "GOUTH4") (pin "8") (pinfunction "8_8") (pintype "passive"))
      (node (ref "GSTP164") (pin "12") (pinfunction "~{OUT7}_12") (pintype "passive"))
    )
    (net (code "127") (name "/GOUT56") (class "Default")
      (node (ref "GOUTH4") (pin "9") (pinfunction "9_9") (pintype "passive"))
      (node (ref "GSTP164") (pin "13") (pinfunction "~{OUT8}_13") (pintype "passive"))
    )
    (net (code "128") (name "/GOUT57") (class "Default")
      (node (ref "GOUTH4") (pin "10") (pinfunction "10_10") (pintype "passive"))
      (node (ref "GSTP164") (pin "14") (pinfunction "~{OUT9}_14") (pintype "passive"))
    )
    (net (code "129") (name "/GOUT58") (class "Default")
      (node (ref "GOUTH4") (pin "11") (pinfunction "11_11") (pintype "passive"))
      (node (ref "GSTP164") (pin "15") (pinfunction "~{OUT10}_15") (pintype "passive"))
    )
    (net (code "130") (name "/GOUT59") (class "Default")
      (node (ref "GOUTH4") (pin "12") (pinfunction "12_12") (pintype "passive"))
      (node (ref "GSTP164") (pin "16") (pinfunction "~{OUT11}_16") (pintype "passive"))
    )
    (net (code "131") (name "/GOUT60") (class "Default")
      (node (ref "GOUTH4") (pin "13") (pinfunction "13_13") (pintype "passive"))
      (node (ref "GSTP164") (pin "17") (pinfunction "~{OUT12}_17") (pintype "passive"))
    )
    (net (code "132") (name "/GOUT61") (class "Default")
      (node (ref "GOUTH4") (pin "14") (pinfunction "14_14") (pintype "passive"))
      (node (ref "GSTP164") (pin "18") (pinfunction "~{OUT13}_18") (pintype "passive"))
    )
    (net (code "133") (name "/GOUT62") (class "Default")
      (node (ref "GOUTH4") (pin "15") (pinfunction "15_15") (pintype "passive"))
      (node (ref "GSTP164") (pin "19") (pinfunction "~{OUT14}_19") (pintype "passive"))
    )
    (net (code "134") (name "/GOUT63") (class "Default")
      (node (ref "GOUTH4") (pin "16") (pinfunction "16_16") (pintype "passive"))
      (node (ref "GSTP164") (pin "20") (pinfunction "~{OUT15}_20") (pintype "passive"))
    )
    (net (code "135") (name "/GREENSPI") (class "Default")
      (node (ref "GSTP161") (pin "2") (pinfunction "SDI_2") (pintype "passive"))
      (node (ref "SPICOM") (pin "5") (pinfunction "5_5") (pintype "passive"))
    )
    (net (code "136") (name "/GREENSPIOUT1") (class "Default")
      (node (ref "GSTP161") (pin "22") (pinfunction "SDO_22") (pintype "passive"))
      (node (ref "GSTP162") (pin "2") (pinfunction "SDI_2") (pintype "passive"))
    )
    (net (code "137") (name "/GREENSPIOUT2") (class "Default")
      (node (ref "GSTP162") (pin "22") (pinfunction "SDO_22") (pintype "passive"))
      (node (ref "GSTP163") (pin "2") (pinfunction "SDI_2") (pintype "passive"))
    )
    (net (code "138") (name "/GREENSPIOUT3") (class "Default")
      (node (ref "GSTP163") (pin "22") (pinfunction "SDO_22") (pintype "passive"))
      (node (ref "GSTP164") (pin "2") (pinfunction "SDI_2") (pintype "passive"))
    )
    (net (code "139") (name "/LATCH") (class "Default")
      (node (ref "BSTP161") (pin "4") (pinfunction "LE/DM1_4") (pintype "passive"))
      (node (ref "BSTP162") (pin "4") (pinfunction "LE/DM1_4") (pintype "passive"))
      (node (ref "BSTP163") (pin "4") (pinfunction "LE/DM1_4") (pintype "passive"))
      (node (ref "BSTP164") (pin "4") (pinfunction "LE/DM1_4") (pintype "passive"))
      (node (ref "GSTP161") (pin "4") (pinfunction "LE/DM1_4") (pintype "passive"))
      (node (ref "GSTP162") (pin "4") (pinfunction "LE/DM1_4") (pintype "passive"))
      (node (ref "GSTP163") (pin "4") (pinfunction "LE/DM1_4") (pintype "passive"))
      (node (ref "GSTP164") (pin "4") (pinfunction "LE/DM1_4") (pintype "passive"))
      (node (ref "RSTP161") (pin "4") (pinfunction "LE/DM1_4") (pintype "passive"))
      (node (ref "RSTP162") (pin "4") (pinfunction "LE/DM1_4") (pintype "passive"))
      (node (ref "RSTP163") (pin "4") (pinfunction "LE/DM1_4") (pintype "passive"))
      (node (ref "RSTP164") (pin "4") (pinfunction "LE/DM1_4") (pintype "passive"))
      (node (ref "SPICOM") (pin "2") (pinfunction "2_2") (pintype "passive"))
    )
    (net (code "141") (name "/OENABLE") (class "Default")
      (node (ref "BSTP161") (pin "21") (pinfunction "~{OE/DM2}_21") (pintype "passive"))
      (node (ref "BSTP162") (pin "21") (pinfunction "~{OE/DM2}_21") (pintype "passive"))
      (node (ref "BSTP163") (pin "21") (pinfunction "~{OE/DM2}_21") (pintype "passive"))
      (node (ref "BSTP164") (pin "21") (pinfunction "~{OE/DM2}_21") (pintype "passive"))
      (node (ref "GSTP161") (pin "21") (pinfunction "~{OE/DM2}_21") (pintype "passive"))
      (node (ref "GSTP162") (pin "21") (pinfunction "~{OE/DM2}_21") (pintype "passive"))
      (node (ref "GSTP163") (pin "21") (pinfunction "~{OE/DM2}_21") (pintype "passive"))
      (node (ref "GSTP164") (pin "21") (pinfunction "~{OE/DM2}_21") (pintype "passive"))
      (node (ref "RSTP161") (pin "21") (pinfunction "~{OE/DM2}_21") (pintype "passive"))
      (node (ref "RSTP162") (pin "21") (pinfunction "~{OE/DM2}_21") (pintype "passive"))
      (node (ref "RSTP163") (pin "21") (pinfunction "~{OE/DM2}_21") (pintype "passive"))
      (node (ref "RSTP164") (pin "21") (pinfunction "~{OE/DM2}_21") (pintype "passive"))
      (node (ref "SPICOM") (pin "3") (pinfunction "3_3") (pintype "passive"))
    )
    (net (code "142") (name "/REDSPI") (class "Default")
      (node (ref "RSTP161") (pin "2") (pinfunction "SDI_2") (pintype "passive"))
      (node (ref "SPICOM") (pin "4") (pinfunction "4_4") (pintype "passive"))
    )
    (net (code "143") (name "/REDSPIOUT1") (class "Default")
      (node (ref "RSTP161") (pin "22") (pinfunction "SDO_22") (pintype "passive"))
      (node (ref "RSTP162") (pin "2") (pinfunction "SDI_2") (pintype "passive"))
    )
    (net (code "144") (name "/REDSPIOUT2") (class "Default")
      (node (ref "RSTP162") (pin "22") (pinfunction "SDO_22") (pintype "passive"))
      (node (ref "RSTP163") (pin "2") (pinfunction "SDI_2") (pintype "passive"))
    )
    (net (code "145") (name "/REDSPIOUT3") (class "Default")
      (node (ref "RSTP163") (pin "22") (pinfunction "SDO_22") (pintype "passive"))
      (node (ref "RSTP164") (pin "2") (pinfunction "SDI_2") (pintype "passive"))
    )
    (net (code "146") (name "/ROUT0") (class "Default")
      (node (ref "ROUTH1") (pin "1") (pinfunction "1_1") (pintype "passive"))
      (node (ref "RSTP161") (pin "5") (pinfunction "~{OUT0}_5") (pintype "passive"))
    )
    (net (code "147") (name "/ROUT1") (class "Default")
      (node (ref "ROUTH1") (pin "2") (pinfunction "2_2") (pintype "passive"))
      (node (ref "RSTP161") (pin "6") (pinfunction "~{OUT1}_6") (pintype "passive"))
    )
    (net (code "148") (name "/ROUT2") (class "Default")
      (node (ref "ROUTH1") (pin "3") (pinfunction "3_3") (pintype "passive"))
      (node (ref "RSTP161") (pin "7") (pinfunction "~{OUT2}_7") (pintype "passive"))
    )
    (net (code "149") (name "/ROUT3") (class "Default")
      (node (ref "ROUTH1") (pin "4") (pinfunction "4_4") (pintype "passive"))
      (node (ref "RSTP161") (pin "8") (pinfunction "~{OUT3}_8") (pintype "passive"))
    )
    (net (code "150") (name "/ROUT4") (class "Default")
      (node (ref "ROUTH1") (pin "5") (pinfunction "5_5") (pintype "passive"))
      (node (ref "RSTP161") (pin "9") (pinfunction "~{OUT4}_9") (pintype "passive"))
    )
    (net (code "151") (name "/ROUT5") (class "Default")
      (node (ref "ROUTH1") (pin "6") (pinfunction "6_6") (pintype "passive"))
      (node (ref "RSTP161") (pin "10") (pinfunction "~{OUT5}_10") (pintype "passive"))
    )
    (net (code "152") (name "/ROUT6") (class "Default")
      (node (ref "ROUTH1") (pin "7") (pinfunction "7_7") (pintype "passive"))
      (node (ref "RSTP161") (pin "11") (pinfunction "~{OUT6}_11") (pintype "passive"))
    )
    (net (code "153") (name "/ROUT7") (class "Default")
      (node (ref "ROUTH1") (pin "8") (pinfunction "8_8") (pintype "passive"))
      (node (ref "RSTP161") (pin "12") (pinfunction "~{OUT7}_12") (pintype "passive"))
    )
    (net (code "154") (name "/ROUT8") (class "Default")
      (node (ref "ROUTH1") (pin "9") (pinfunction "9_9") (pintype "passive"))
      (node (ref "RSTP161") (pin "13") (pinfunction "~{OUT8}_13") (pintype "passive"))
    )
    (net (code "155") (name "/ROUT9") (class "Default")
      (node (ref "ROUTH1") (pin "10") (pinfunction "10_10") (pintype "passive"))
      (node (ref "RSTP161") (pin "14") (pinfunction "~{OUT9}_14") (pintype "passive"))
    )
    (net (code "156") (name "/ROUT10") (class "Default")
      (node (ref "ROUTH1") (pin "11") (pinfunction "11_11") (pintype "passive"))
      (node (ref "RSTP161") (pin "15") (pinfunction "~{OUT10}_15") (pintype "passive"))
    )
    (net (code "157") (name "/ROUT11") (class "Default")
      (node (ref "ROUTH1") (pin "12") (pinfunction "12_12") (pintype "passive"))
      (node (ref "RSTP161") (pin "16") (pinfunction "~{OUT11}_16") (pintype "passive"))
    )
    (net (code "158") (name "/ROUT12") (class "Default")
      (node (ref "ROUTH1") (pin "13") (pinfunction "13_13") (pintype "passive"))
      (node (ref "RSTP161") (pin "17") (pinfunction "~{OUT12}_17") (pintype "passive"))
    )
    (net (code "159") (name "/ROUT13") (class "Default")
      (node (ref "ROUTH1") (pin "14") (pinfunction "14_14") (pintype "passive"))
      (node (ref "RSTP161") (pin "18") (pinfunction "~{OUT13}_18") (pintype "passive"))
    )
    (net (code "160") (name "/ROUT14") (class "Default")
      (node (ref "ROUTH1") (pin "15") (pinfunction "15_15") (pintype "passive"))
      (node (ref "RSTP161") (pin "19") (pinfunction "~{OUT14}_19") (pintype "passive"))
    )
    (net (code "161") (name "/ROUT15") (class "Default")
      (node (ref "ROUTH1") (pin "16") (pinfunction "16_16") (pintype "passive"))
      (node (ref "RSTP161") (pin "20") (pinfunction "~{OUT15}_20") (pintype "passive"))
    )
    (net (code "162") (name "/ROUT16") (class "Default")
      (node (ref "ROUTH2") (pin "1") (pinfunction "1_1") (pintype "passive"))
      (node (ref "RSTP162") (pin "5") (pinfunction "~{OUT0}_5") (pintype "passive"))
    )
    (net (code "163") (name "/ROUT17") (class "Default")
      (node (ref "ROUTH2") (pin "2") (pinfunction "2_2") (pintype "passive"))
      (node (ref "RSTP162") (pin "6") (pinfunction "~{OUT1}_6") (pintype "passive"))
    )
    (net (code "164") (name "/ROUT18") (class "Default")
      (node (ref "ROUTH2") (pin "3") (pinfunction "3_3") (pintype "passive"))
      (node (ref "RSTP162") (pin "7") (pinfunction "~{OUT2}_7") (pintype "passive"))
    )
    (net (code "165") (name "/ROUT19") (class "Default")
      (node (ref "ROUTH2") (pin "4") (pinfunction "4_4") (pintype "passive"))
      (node (ref "RSTP162") (pin "8") (pinfunction "~{OUT3}_8") (pintype "passive"))
    )
    (net (code "166") (name "/ROUT20") (class "Default")
      (node (ref "ROUTH2") (pin "5") (pinfunction "5_5") (pintype "passive"))
      (node (ref "RSTP162") (pin "9") (pinfunction "~{OUT4}_9") (pintype "passive"))
    )
    (net (code "167") (name "/ROUT21") (class "Default")
      (node (ref "ROUTH2") (pin "6") (pinfunction "6_6") (pintype "passive"))
      (node (ref "RSTP162") (pin "10") (pinfunction "~{OUT5}_10") (pintype "passive"))
    )
    (net (code "168") (name "/ROUT22") (class "Default")
      (node (ref "ROUTH2") (pin "7") (pinfunction "7_7") (pintype "passive"))
      (node (ref "RSTP162") (pin "11") (pinfunction "~{OUT6}_11") (pintype "passive"))
    )
    (net (code "169") (name "/ROUT23") (class "Default")
      (node (ref "ROUTH2") (pin "8") (pinfunction "8_8") (pintype "passive"))
      (node (ref "RSTP162") (pin "12") (pinfunction "~{OUT7}_12") (pintype "passive"))
    )
    (net (code "170") (name "/ROUT24") (class "Default")
      (node (ref "ROUTH2") (pin "9") (pinfunction "9_9") (pintype "passive"))
      (node (ref "RSTP162") (pin "13") (pinfunction "~{OUT8}_13") (pintype "passive"))
    )
    (net (code "171") (name "/ROUT25") (class "Default")
      (node (ref "ROUTH2") (pin "10") (pinfunction "10_10") (pintype "passive"))
      (node (ref "RSTP162") (pin "14") (pinfunction "~{OUT9}_14") (pintype "passive"))
    )
    (net (code "172") (name "/ROUT26") (class "Default")
      (node (ref "ROUTH2") (pin "11") (pinfunction "11_11") (pintype "passive"))
      (node (ref "RSTP162") (pin "15") (pinfunction "~{OUT10}_15") (pintype "passive"))
    )
    (net (code "173") (name "/ROUT27") (class "Default")
      (node (ref "ROUTH2") (pin "12") (pinfunction "12_12") (pintype "passive"))
      (node (ref "RSTP162") (pin "16") (pinfunction "~{OUT11}_16") (pintype "passive"))
    )
    (net (code "174") (name "/ROUT28") (class "Default")
      (node (ref "ROUTH2") (pin "13") (pinfunction "13_13") (pintype "passive"))
      (node (ref "RSTP162") (pin "17") (pinfunction "~{OUT12}_17") (pintype "passive"))
    )
    (net (code "175") (name "/ROUT29") (class "Default")
      (node (ref "ROUTH2") (pin "14") (pinfunction "14_14") (pintype "passive"))
      (node (ref "RSTP162") (pin "18") (pinfunction "~{OUT13}_18") (pintype "passive"))
    )
    (net (code "176") (name "/ROUT30") (class "Default")
      (node (ref "ROUTH2") (pin "15") (pinfunction "15_15") (pintype "passive"))
      (node (ref "RSTP162") (pin "19") (pinfunction "~{OUT14}_19") (pintype "passive"))
    )
    (net (code "177") (name "/ROUT31") (class "Default")
      (node (ref "ROUTH2") (pin "16") (pinfunction "16_16") (pintype "passive"))
      (node (ref "RSTP162") (pin "20") (pinfunction "~{OUT15}_20") (pintype "passive"))
    )
    (net (code "178") (name "/ROUT32") (class "Default")
      (node (ref "ROUTH3") (pin "1") (pinfunction "1_1") (pintype "passive"))
      (node (ref "RSTP163") (pin "5") (pinfunction "~{OUT0}_5") (pintype "passive"))
    )
    (net (code "179") (name "/ROUT33") (class "Default")
      (node (ref "ROUTH3") (pin "2") (pinfunction "2_2") (pintype "passive"))
      (node (ref "RSTP163") (pin "6") (pinfunction "~{OUT1}_6") (pintype "passive"))
    )
    (net (code "180") (name "/ROUT34") (class "Default")
      (node (ref "ROUTH3") (pin "3") (pinfunction "3_3") (pintype "passive"))
      (node (ref "RSTP163") (pin "7") (pinfunction "~{OUT2}_7") (pintype "passive"))
    )
    (net (code "181") (name "/ROUT35") (class "Default")
      (node (ref "ROUTH3") (pin "4") (pinfunction "4_4") (pintype "passive"))
      (node (ref "RSTP163") (pin "8") (pinfunction "~{OUT3}_8") (pintype "passive"))
    )
    (net (code "182") (name "/ROUT36") (class "Default")
      (node (ref "ROUTH3") (pin "5") (pinfunction "5_5") (pintype "passive"))
      (node (ref "RSTP163") (pin "9") (pinfunction "~{OUT4}_9") (pintype "passive"))
    )
    (net (code "183") (name "/ROUT37") (class "Default")
      (node (ref "ROUTH3") (pin "6") (pinfunction "6_6") (pintype "passive"))
      (node (ref "RSTP163") (pin "10") (pinfunction "~{OUT5}_10") (pintype "passive"))
    )
    (net (code "184") (name "/ROUT38") (class "Default")
      (node (ref "ROUTH3") (pin "7") (pinfunction "7_7") (pintype "passive"))
      (node (ref "RSTP163") (pin "11") (pinfunction "~{OUT6}_11") (pintype "passive"))
    )
    (net (code "185") (name "/ROUT39") (class "Default")
      (node (ref "ROUTH3") (pin "8") (pinfunction "8_8") (pintype "passive"))
      (node (ref "RSTP163") (pin "12") (pinfunction "~{OUT7}_12") (pintype "passive"))
    )
    (net (code "186") (name "/ROUT40") (class "Default")
      (node (ref "ROUTH3") (pin "9") (pinfunction "9_9") (pintype "passive"))
      (node (ref "RSTP163") (pin "13") (pinfunction "~{OUT8}_13") (pintype "passive"))
    )
    (net (code "187") (name "/ROUT41") (class "Default")
      (node (ref "ROUTH3") (pin "10") (pinfunction "10_10") (pintype "passive"))
      (node (ref "RSTP163") (pin "14") (pinfunction "~{OUT9}_14") (pintype "passive"))
    )
    (net (code "188") (name "/ROUT42") (class "Default")
      (node (ref "ROUTH3") (pin "11") (pinfunction "11_11") (pintype "passive"))
      (node (ref "RSTP163") (pin "15") (pinfunction "~{OUT10}_15") (pintype "passive"))
    )
    (net (code "189") (name "/ROUT43") (class "Default")
      (node (ref "ROUTH3") (pin "12") (pinfunction "12_12") (pintype "passive"))
      (node (ref "RSTP163") (pin "16") (pinfunction "~{OUT11}_16") (pintype "passive"))
    )
    (net (code "190") (name "/ROUT44") (class "Default")
      (node (ref "ROUTH3") (pin "13") (pinfunction "13_13") (pintype "passive"))
      (node (ref "RSTP163") (pin "17") (pinfunction "~{OUT12}_17") (pintype "passive"))
    )
    (net (code "191") (name "/ROUT45") (class "Default")
      (node (ref "ROUTH3") (pin "14") (pinfunction "14_14") (pintype "passive"))
      (node (ref "RSTP163") (pin "18") (pinfunction "~{OUT13}_18") (pintype "passive"))
    )
    (net (code "192") (name "/ROUT46") (class "Default")
      (node (ref "ROUTH3") (pin "15") (pinfunction "15_15") (pintype "passive"))
      (node (ref "RSTP163") (pin "19") (pinfunction "~{OUT14}_19") (pintype "passive"))
    )
    (net (code "193") (name "/ROUT47") (class "Default")
      (node (ref "ROUTH3") (pin "16") (pinfunction "16_16") (pintype "passive"))
      (node (ref "RSTP163") (pin "20") (pinfunction "~{OUT15}_20") (pintype "passive"))
    )
    (net (code "194") (name "/ROUT48") (class "Default")
      (node (ref "ROUTH4") (pin "1") (pinfunction "1_1") (pintype "passive"))
      (node (ref "RSTP164") (pin "5") (pinfunction "~{OUT0}_5") (pintype "passive"))
    )
    (net (code "195") (name "/ROUT49") (class "Default")
      (node (ref "ROUTH4") (pin "2") (pinfunction "2_2") (pintype "passive"))
      (node (ref "RSTP164") (pin "6") (pinfunction "~{OUT1}_6") (pintype "passive"))
    )
    (net (code "196") (name "/ROUT50") (class "Default")
      (node (ref "ROUTH4") (pin "3") (pinfunction "3_3") (pintype "passive"))
      (node (ref "RSTP164") (pin "7") (pinfunction "~{OUT2}_7") (pintype "passive"))
    )
    (net (code "197") (name "/ROUT51") (class "Default")
      (node (ref "ROUTH4") (pin "4") (pinfunction "4_4") (pintype "passive"))
      (node (ref "RSTP164") (pin "8") (pinfunction "~{OUT3}_8") (pintype "passive"))
    )
    (net (code "198") (name "/ROUT52") (class "Default")
      (node (ref "ROUTH4") (pin "5") (pinfunction "5_5") (pintype "passive"))
      (node (ref "RSTP164") (pin "9") (pinfunction "~{OUT4}_9") (pintype "passive"))
    )
    (net (code "199") (name "/ROUT53") (class "Default")
      (node (ref "ROUTH4") (pin "6") (pinfunction "6_6") (pintype "passive"))
      (node (ref "RSTP164") (pin "10") (pinfunction "~{OUT5}_10") (pintype "passive"))
    )
    (net (code "200") (name "/ROUT54") (class "Default")
      (node (ref "ROUTH4") (pin "7") (pinfunction "7_7") (pintype "passive"))
      (node (ref "RSTP164") (pin "11") (pinfunction "~{OUT6}_11") (pintype "passive"))
    )
    (net (code "201") (name "/ROUT55") (class "Default")
      (node (ref "ROUTH4") (pin "8") (pinfunction "8_8") (pintype "passive"))
      (node (ref "RSTP164") (pin "12") (pinfunction "~{OUT7}_12") (pintype "passive"))
    )
    (net (code "202") (name "/ROUT56") (class "Default")
      (node (ref "ROUTH4") (pin "9") (pinfunction "9_9") (pintype "passive"))
      (node (ref "RSTP164") (pin "13") (pinfunction "~{OUT8}_13") (pintype "passive"))
    )
    (net (code "203") (name "/ROUT57") (class "Default")
      (node (ref "ROUTH4") (pin "10") (pinfunction "10_10") (pintype "passive"))
      (node (ref "RSTP164") (pin "14") (pinfunction "~{OUT9}_14") (pintype "passive"))
    )
    (net (code "204") (name "/ROUT58") (class "Default")
      (node (ref "ROUTH4") (pin "11") (pinfunction "11_11") (pintype "passive"))
      (node (ref "RSTP164") (pin "15") (pinfunction "~{OUT10}_15") (pintype "passive"))
    )
    (net (code "205") (name "/ROUT59") (class "Default")
      (node (ref "ROUTH4") (pin "12") (pinfunction "12_12") (pintype "passive"))
      (node (ref "RSTP164") (pin "16") (pinfunction "~{OUT11}_16") (pintype "passive"))
    )
    (net (code "206") (name "/ROUT60") (class "Default")
      (node (ref "ROUTH4") (pin "13") (pinfunction "13_13") (pintype "passive"))
      (node (ref "RSTP164") (pin "17") (pinfunction "~{OUT12}_17") (pintype "passive"))
    )
    (net (code "207") (name "/ROUT61") (class "Default")
      (node (ref "ROUTH4") (pin "14") (pinfunction "14_14") (pintype "passive"))
      (node (ref "RSTP164") (pin "18") (pinfunction "~{OUT13}_18") (pintype "passive"))
    )
    (net (code "208") (name "/ROUT62") (class "Default")
      (node (ref "ROUTH4") (pin "15") (pinfunction "15_15") (pintype "passive"))
      (node (ref "RSTP164") (pin "19") (pinfunction "~{OUT14}_19") (pintype "passive"))
    )
    (net (code "209") (name "/ROUT63") (class "Default")
      (node (ref "ROUTH4") (pin "16") (pinfunction "16_16") (pintype "passive"))
      (node (ref "RSTP164") (pin "20") (pinfunction "~{OUT15}_20") (pintype "passive"))
    )
    (net (code "210") (name "GND") (class "Default")
      (node (ref "BSTP161") (pin "1") (pinfunction "GND_1") (pintype "passive"))
      (node (ref "BSTP162") (pin "1") (pinfunction "GND_1") (pintype "passive"))
      (node (ref "BSTP163") (pin "1") (pinfunction "GND_1") (pintype "passive"))
      (node (ref "BSTP164") (pin "1") (pinfunction "GND_1") (pintype "passive"))
      (node (ref "C1") (pin "1") (pinfunction "1_1") (pintype "passive"))
      (node (ref "C10") (pin "1") (pinfunction "1_1") (pintype "passive"))
      (node (ref "C11") (pin "1") (pinfunction "1_1") (pintype "passive"))
      (node (ref "C12") (pin "1") (pinfunction "1_1") (pintype "passive"))
      (node (ref "C2") (pin "1") (pinfunction "1_1") (pintype "passive"))
      (node (ref "C3") (pin "1") (pinfunction "1_1") (pintype "passive"))
      (node (ref "C4") (pin "1") (pinfunction "1_1") (pintype "passive"))
      (node (ref "C5") (pin "1") (pinfunction "1_1") (pintype "passive"))
      (node (ref "C6") (pin "1") (pinfunction "1_1") (pintype "passive"))
      (node (ref "C7") (pin "1") (pinfunction "1_1") (pintype "passive"))
      (node (ref "C8") (pin "1") (pinfunction "1_1") (pintype "passive"))
      (node (ref "C9") (pin "1") (pinfunction "1_1") (pintype "passive"))
      (node (ref "GSTP161") (pin "1") (pinfunction "GND_1") (pintype "passive"))
      (node (ref "GSTP162") (pin "1") (pinfunction "GND_1") (pintype "passive"))
      (node (ref "GSTP163") (pin "1") (pinfunction "GND_1") (pintype "passive"))
      (node (ref "GSTP164") (pin "1") (pinfunction "GND_1") (pintype "passive"))
      (node (ref "R1") (pin "2") (pinfunction "2_2") (pintype "passive"))
      (node (ref "R10") (pin "2") (pinfunction "2_2") (pintype "passive"))
      (node (ref "R11") (pin "2") (pinfunction "2_2") (pintype "passive"))
      (node (ref "R12") (pin "2") (pinfunction "2_2") (pintype "passive"))
      (node (ref "R2") (pin "2") (pinfunction "2_2") (pintype "passive"))
      (node (ref "R3") (pin "2") (pinfunction "2_2") (pintype "passive"))
      (node (ref "R4") (pin "2") (pinfunction "2_2") (pintype "passive"))
      (node (ref "R5") (pin "2") (pinfunction "2_2") (pintype "passive"))
      (node (ref "R6") (pin "2") (pinfunction "2_2") (pintype "passive"))
      (node (ref "R7") (pin "2") (pinfunction "2_2") (pintype "passive"))
      (node (ref "R8") (pin "2") (pinfunction "2_2") (pintype "passive"))
      (node (ref "R9") (pin "2") (pinfunction "2_2") (pintype "passive"))
      (node (ref "RSTP161") (pin "1") (pinfunction "GND_1") (pintype "passive"))
      (node (ref "RSTP162") (pin "1") (pinfunction "GND_1") (pintype "passive"))
      (node (ref "RSTP163") (pin "1") (pinfunction "GND_1") (pintype "passive"))
      (node (ref "RSTP164") (pin "1") (pinfunction "GND_1") (pintype "passive"))
      (node (ref "Terminal Block") (pin "3") (pinfunction "pin3_3") (pintype "passive"))
    )
    (net (code "211") (name "Net-(BSTP161-R-EXT)") (class "Default")
      (node (ref "BSTP161") (pin "23") (pinfunction "R-EXT_23") (pintype "passive"))
      (node (ref "R9") (pin "1") (pinfunction "1_1") (pintype "passive"))
    )
    (net (code "212") (name "Net-(BSTP162-R-EXT)") (class "Default")
      (node (ref "BSTP162") (pin "23") (pinfunction "R-EXT_23") (pintype "passive"))
      (node (ref "R10") (pin "1") (pinfunction "1_1") (pintype "passive"))
    )
    (net (code "213") (name "Net-(BSTP163-R-EXT)") (class "Default")
      (node (ref "BSTP163") (pin "23") (pinfunction "R-EXT_23") (pintype "passive"))
      (node (ref "R11") (pin "1") (pinfunction "1_1") (pintype "passive"))
    )
    (net (code "214") (name "Net-(BSTP164-R-EXT)") (class "Default")
      (node (ref "BSTP164") (pin "23") (pinfunction "R-EXT_23") (pintype "passive"))
      (node (ref "R12") (pin "1") (pinfunction "1_1") (pintype "passive"))
    )
    (net (code "215") (name "Net-(GSTP161-R-EXT)") (class "Default")
      (node (ref "GSTP161") (pin "23") (pinfunction "R-EXT_23") (pintype "passive"))
      (node (ref "R5") (pin "1") (pinfunction "1_1") (pintype "passive"))
    )
    (net (code "216") (name "Net-(GSTP162-R-EXT)") (class "Default")
      (node (ref "GSTP162") (pin "23") (pinfunction "R-EXT_23") (pintype "passive"))
      (node (ref "R6") (pin "1") (pinfunction "1_1") (pintype "passive"))
    )
    (net (code "217") (name "Net-(GSTP163-R-EXT)") (class "Default")
      (node (ref "GSTP163") (pin "23") (pinfunction "R-EXT_23") (pintype "passive"))
      (node (ref "R7") (pin "1") (pinfunction "1_1") (pintype "passive"))
    )
    (net (code "218") (name "Net-(GSTP164-R-EXT)") (class "Default")
      (node (ref "GSTP164") (pin "23") (pinfunction "R-EXT_23") (pintype "passive"))
      (node (ref "R8") (pin "1") (pinfunction "1_1") (pintype "passive"))
    )
    (net (code "219") (name "Net-(RSTP161-R-EXT)") (class "Default")
      (node (ref "R1") (pin "1") (pinfunction "1_1") (pintype "passive"))
      (node (ref "RSTP161") (pin "23") (pinfunction "R-EXT_23") (pintype "passive"))
    )
    (net (code "220") (name "Net-(RSTP162-R-EXT)") (class "Default")
      (node (ref "R2") (pin "1") (pinfunction "1_1") (pintype "passive"))
      (node (ref "RSTP162") (pin "23") (pinfunction "R-EXT_23") (pintype "passive"))
    )
    (net (code "221") (name "Net-(RSTP163-R-EXT)") (class "Default")
      (node (ref "R3") (pin "1") (pinfunction "1_1") (pintype "passive"))
      (node (ref "RSTP163") (pin "23") (pinfunction "R-EXT_23") (pintype "passive"))
    )
    (net (code "222") (name "Net-(RSTP164-R-EXT)") (class "Default")
      (node (ref "R4") (pin "1") (pinfunction "1_1") (pintype "passive"))
      (node (ref "RSTP164") (pin "23") (pinfunction "R-EXT_23") (pintype "passive"))
    )
    (net (code "223") (name "unconnected-(BSTP164-SDO-Pad22)") (class "Default")
      (node (ref "BSTP164") (pin "22") (pinfunction "SDO_22") (pintype "passive"))
    )
    (net (code "224") (name "unconnected-(GSTP164-SDO-Pad22)") (class "Default")
      (node (ref "GSTP164") (pin "22") (pinfunction "SDO_22") (pintype "passive"))
    )
    (net (code "225") (name "unconnected-(RSTP164-SDO-Pad22)") (class "Default")
      (node (ref "RSTP164") (pin "22") (pinfunction "SDO_22") (pintype "passive"))
    )
    (net (code "226") (name "unconnected-(Terminal Block-pin2-Pad2)") (class "Default")
      (node (ref "Terminal Block") (pin "2") (pinfunction "pin2_2") (pintype "passive"))
    )
  )
)
